# ESP-01_Slim.net
KiCad netlist of a schematic drawn in EAGLE
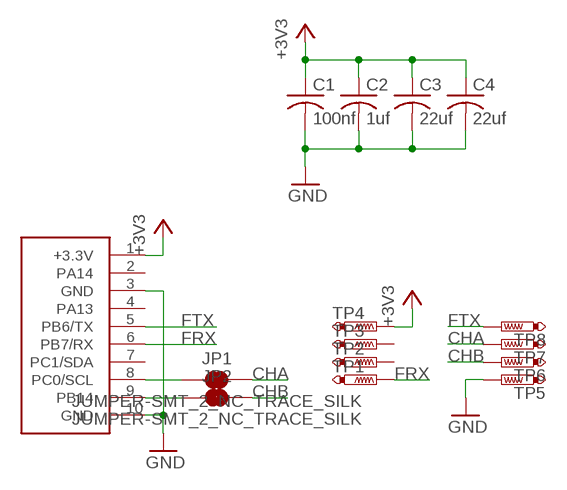
[diagram p0: schematic, sheet 1]

(export (version "E")
  (design (tool "Eeschema 10.0.6"))
  (components
    (comp (ref "C1")
      (value "100nf")
      (footprint "eagle-import:C0805")
      (libsource (lib "eagle-import") (part "C-USC0805"))
    )
    (comp (ref "C2")
      (value "1uf")
      (footprint "eagle-import:C0805")
      (libsource (lib "eagle-import") (part "C-USC0805"))
    )
    (comp (ref "C3")
      (value "22uf")
      (footprint "eagle-import:C3216")
      (libsource (lib "eagle-import") (part "C-USC3216"))
    )
    (comp (ref "C4")
      (value "22uf")
      (footprint "eagle-import:C3216")
      (libsource (lib "eagle-import") (part "C-USC3216"))
    )
    (comp (ref "JP1")
      (value "JUMPER-SMT_2_NC_TRACE_SILK")
      (footprint "eagle-import:SMT-JUMPER_2_NC_TRACE_SILK")
      (libsource (lib "eagle-import") (part "JUMPER-SMT_2_NC_TRACE_SILK"))
    )
    (comp (ref "JP2")
      (value "JUMPER-SMT_2_NC_TRACE_SILK")
      (footprint "eagle-import:SMT-JUMPER_2_NC_TRACE_SILK")
      (libsource (lib "eagle-import") (part "JUMPER-SMT_2_NC_TRACE_SILK"))
    )
    (comp (ref "TP1")
      (value "PTR1B1,27")
      (footprint "eagle-import:B1,27")
      (libsource (lib "eagle-import") (part "PTR1B1,27"))
    )
    (comp (ref "TP2")
      (value "PTR1B1,27")
      (footprint "eagle-import:B1,27")
      (libsource (lib "eagle-import") (part "PTR1B1,27"))
    )
    (comp (ref "TP3")
      (value "PTR1B1,27")
      (footprint "eagle-import:B1,27")
      (libsource (lib "eagle-import") (part "PTR1B1,27"))
    )
    (comp (ref "TP4")
      (value "PTR1B1,27")
      (footprint "eagle-import:B1,27")
      (libsource (lib "eagle-import") (part "PTR1B1,27"))
    )
    (comp (ref "TP5")
      (value "PTR1B1,27")
      (footprint "eagle-import:B1,27")
      (libsource (lib "eagle-import") (part "PTR1B1,27"))
    )
    (comp (ref "TP6")
      (value "PTR1B1,27")
      (footprint "eagle-import:B1,27")
      (libsource (lib "eagle-import") (part "PTR1B1,27"))
    )
    (comp (ref "TP7")
      (value "PTR1B1,27")
      (footprint "eagle-import:B1,27")
      (libsource (lib "eagle-import") (part "PTR1B1,27"))
    )
    (comp (ref "TP8")
      (value "PTR1B1,27")
      (footprint "eagle-import:B1,27")
      (libsource (lib "eagle-import") (part "PTR1B1,27"))
    )
    (comp (ref "U$2")
      (value "RIGHT-H2-SMD")
      (footprint "eagle-import:RIGHT-H2-SMD")
      (libsource (lib "eagle-import") (part "RIGHT-H2-SMD"))
    )
  )
  (nets
    (net (code "1") (name "+3V3") (class "Default")
      (node (ref "C1") (pin "1") (pinfunction "1_1") (pintype "passive"))
      (node (ref "C2") (pin "1") (pinfunction "1_1") (pintype "passive"))
      (node (ref "C3") (pin "1") (pinfunction "1_1") (pintype "passive"))
      (node (ref "C4") (pin "1") (pinfunction "1_1") (pintype "passive"))
      (node (ref "TP4") (pin "TP") (pinfunction "TP_TP") (pintype "input"))
      (node (ref "U$2") (pin "1") (pinfunction "+3.3V_1") (pintype "bidirectional"))
    )
    (net (code "2") (name "/CHA") (class "Default")
      (node (ref "JP1") (pin "2") (pinfunction "2_2") (pintype "passive"))
      (node (ref "TP7") (pin "TP") (pinfunction "TP_TP") (pintype "input"))
    )
    (net (code "3") (name "/CHB") (class "Default")
      (node (ref "JP2") (pin "2") (pinfunction "2_2") (pintype "passive"))
      (node (ref "TP6") (pin "TP") (pinfunction "TP_TP") (pintype "input"))
    )
    (net (code "4") (name "/FRX") (class "Default")
      (node (ref "TP1") (pin "TP") (pinfunction "TP_TP") (pintype "input"))
      (node (ref "U$2") (pin "6") (pinfunction "PB7/RX_6") (pintype "bidirectional"))
    )
    (net (code "5") (name "/FTX") (class "Default")
      (node (ref "TP8") (pin "TP") (pinfunction "TP_TP") (pintype "input"))
      (node (ref "U$2") (pin "5") (pinfunction "PB6/TX_5") (pintype "bidirectional"))
    )
    (net (code "6") (name "GND") (class "Default")
      (node (ref "C1") (pin "2") (pinfunction "2_2") (pintype "passive"))
      (node (ref "C2") (pin "2") (pinfunction "2_2") (pintype "passive"))
      (node (ref "C3") (pin "2") (pinfunction "2_2") (pintype "passive"))
      (node (ref "C4") (pin "2") (pinfunction "2_2") (pintype "passive"))
      (node (ref "TP5") (pin "TP") (pinfunction "TP_TP") (pintype "input"))
      (node (ref "U$2") (pin "10") (pinfunction "GND_10") (pintype "bidirectional"))
      (node (ref "U$2") (pin "3") (pinfunction "GND_3") (pintype "bidirectional"))
    )
    (net (code "7") (name "Net-(U$2-PB14)") (class "Default")
      (node (ref "JP2") (pin "1") (pinfunction "1_1") (pintype "passive"))
      (node (ref "U$2") (pin "9") (pinfunction "PB14_9") (pintype "bidirectional"))
    )
    (net (code "8") (name "Net-(U$2-PC0{slash}SCL)") (class "Default")
      (node (ref "JP1") (pin "1") (pinfunction "1_1") (pintype "passive"))
      (node (ref "U$2") (pin "8") (pinfunction "PC0/SCL_8") (pintype "bidirectional"))
    )
    (net (code "9") (name "unconnected-(TP2-PadTP)") (class "Default")
      (node (ref "TP2") (pin "TP") (pinfunction "TP_TP") (pintype "input"))
    )
    (net (code "10") (name "unconnected-(TP3-PadTP)") (class "Default")
      (node (ref "TP3") (pin "TP") (pinfunction "TP_TP") (pintype "input"))
    )
    (net (code "11") (name "unconnected-(U$2-PA13-Pad4)") (class "Default")
      (node (ref "U$2") (pin "4") (pinfunction "PA13_4") (pintype "bidirectional"))
    )
    (net (code "12") (name "unconnected-(U$2-PA14-Pad2)") (class "Default")
      (node (ref "U$2") (pin "2") (pinfunction "PA14_2") (pintype "bidirectional"))
    )
    (net (code "13") (name "unconnected-(U$2-PC1{slash}SDA-Pad7)") (class "Default")
      (node (ref "U$2") (pin "7") (pinfunction "PC1/SDA_7") (pintype "bidirectional"))
    )
  )
)
